# Motor-Driver.net
KiCad netlist of a schematic drawn in EAGLE
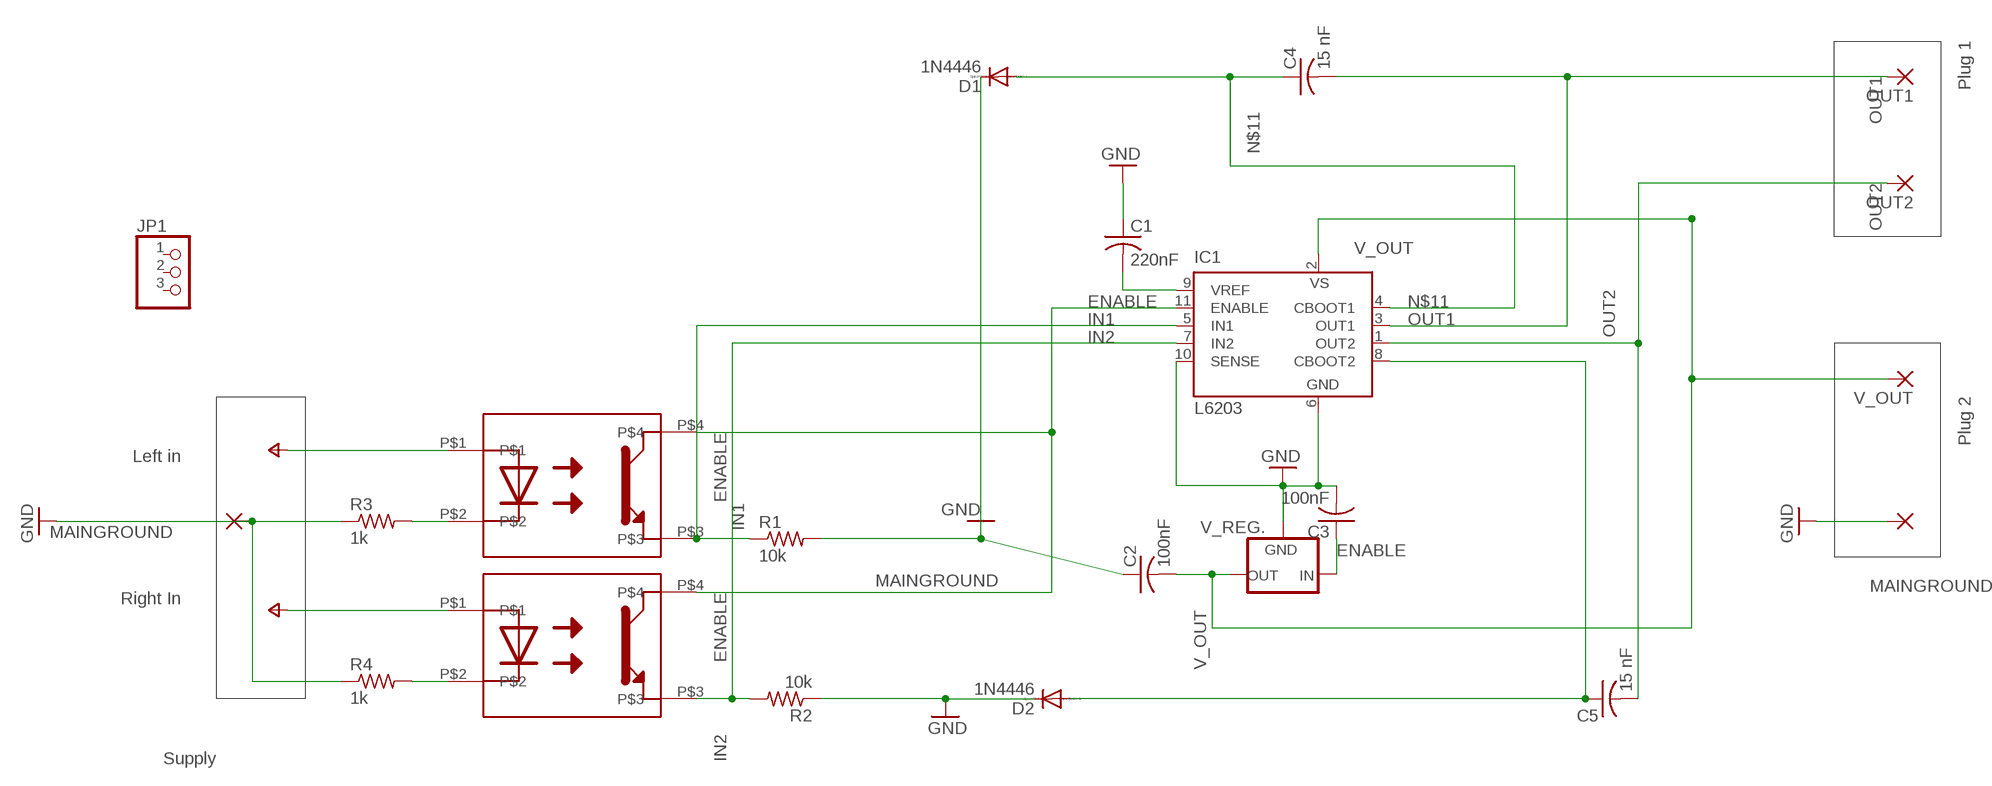
[diagram p0: schematic, sheet 1]

(export (version "E")
  (design (tool "Eeschema 10.0.6"))
  (components
    (comp (ref "C1")
      (value "220nF")
      (footprint "eagle-import:C075-032X103")
      (libsource (lib "eagle-import") (part "C-US075-032X103"))
    )
    (comp (ref "C2")
      (value "100nF")
      (footprint "eagle-import:C075-032X103")
      (libsource (lib "eagle-import") (part "C-US075-032X103"))
    )
    (comp (ref "C3")
      (value "100nF")
      (footprint "eagle-import:C075-032X103")
      (libsource (lib "eagle-import") (part "C-US075-032X103"))
    )
    (comp (ref "C4")
      (value "15 nF")
      (footprint "eagle-import:C075-032X103")
      (libsource (lib "eagle-import") (part "C-US075-032X103"))
    )
    (comp (ref "C5")
      (value "15 nF")
      (footprint "eagle-import:C075-032X103")
      (libsource (lib "eagle-import") (part "C-US075-032X103"))
    )
    (comp (ref "D1")
      (value "1N4446")
      (footprint "eagle-import:DO35-10")
      (libsource (lib "eagle-import") (part "1N4446"))
    )
    (comp (ref "D2")
      (value "1N4446")
      (footprint "eagle-import:DO35-10")
      (libsource (lib "eagle-import") (part "1N4446"))
    )
    (comp (ref "IC1")
      (value "L6203")
      (footprint "eagle-import:MULTIWATT-11")
      (libsource (lib "eagle-import") (part "L6203"))
    )
    (comp (ref "JP1")
      (value "PINHD-1X3")
      (footprint "eagle-import:1X03")
      (libsource (lib "eagle-import") (part "PINHD-1X3"))
    )
    (comp (ref "MAINGROUND")
      (value "PAD-TERMINAL")
      (footprint "eagle-import:2,54_1,1")
      (libsource (lib "eagle-import") (part "PAD-TERMINAL"))
    )
    (comp (ref "OUT1")
      (value "PAD-TERMINAL")
      (footprint "eagle-import:2,54_1,1")
      (libsource (lib "eagle-import") (part "PAD-TERMINAL"))
    )
    (comp (ref "OUT2")
      (value "PAD-TERMINAL")
      (footprint "eagle-import:2,54_1,1")
      (libsource (lib "eagle-import") (part "PAD-TERMINAL"))
    )
    (comp (ref "OUT_GND")
      (value "PAD-TERMINAL")
      (footprint "eagle-import:2,54_1,1")
      (libsource (lib "eagle-import") (part "PAD-TERMINAL"))
    )
    (comp (ref "R1")
      (value "10k")
      (footprint "eagle-import:0204_7")
      (libsource (lib "eagle-import") (part "R-US_0204/7"))
    )
    (comp (ref "R2")
      (value "10k")
      (footprint "eagle-import:0204_7")
      (libsource (lib "eagle-import") (part "R-US_0204/7"))
    )
    (comp (ref "R3")
      (value "1k")
      (footprint "eagle-import:0204_7")
      (libsource (lib "eagle-import") (part "R-US_0204/7"))
    )
    (comp (ref "R4")
      (value "1k")
      (footprint "eagle-import:0204_7")
      (libsource (lib "eagle-import") (part "R-US_0204/7"))
    )
    (comp (ref "U$1")
      (value "TPL521")
      (footprint "eagle-import:TPL521")
      (libsource (lib "eagle-import") (part "TPL521"))
    )
    (comp (ref "U$2")
      (value "TPL521")
      (footprint "eagle-import:TPL521")
      (libsource (lib "eagle-import") (part "TPL521"))
    )
    (comp (ref "V_OUT")
      (value "PAD-TERMINAL")
      (footprint "eagle-import:2,54_1,1")
      (libsource (lib "eagle-import") (part "PAD-TERMINAL"))
    )
    (comp (ref "V_REG.")
      (value "V_REG_78XXTO-92_UNTESTED")
      (footprint "eagle-import:TO-92")
      (libsource (lib "eagle-import") (part "V_REG_78XXTO-92_UNTESTED"))
    )
  )
  (nets
    (net (code "1") (name "/ENABLE") (class "Default")
      (node (ref "C3") (pin "1") (pinfunction "1_1") (pintype "passive"))
      (node (ref "IC1") (pin "11") (pinfunction "ENABLE_11") (pintype "input"))
      (node (ref "U$1") (pin "P$4") (pinfunction "P$4_P$4") (pintype "bidirectional"))
      (node (ref "U$2") (pin "P$4") (pinfunction "P$4_P$4") (pintype "bidirectional"))
      (node (ref "V_REG.") (pin "3") (pinfunction "IN_3") (pintype "input"))
    )
    (net (code "2") (name "/IN1") (class "Default")
      (node (ref "IC1") (pin "5") (pinfunction "IN1_5") (pintype "input"))
      (node (ref "R1") (pin "1") (pinfunction "1_1") (pintype "passive"))
      (node (ref "U$1") (pin "P$3") (pinfunction "P$3_P$3") (pintype "bidirectional"))
    )
    (net (code "3") (name "/IN2") (class "Default")
      (node (ref "IC1") (pin "7") (pinfunction "IN2_7") (pintype "input"))
      (node (ref "R2") (pin "2") (pinfunction "2_2") (pintype "passive"))
      (node (ref "U$2") (pin "P$3") (pinfunction "P$3_P$3") (pintype "bidirectional"))
    )
    (net (code "4") (name "/N$11") (class "Default")
      (node (ref "C4") (pin "1") (pinfunction "1_1") (pintype "passive"))
      (node (ref "D1") (pin "A") (pinfunction "A_A") (pintype "passive"))
      (node (ref "IC1") (pin "4") (pinfunction "CBOOT1_4") (pintype "input"))
    )
    (net (code "5") (name "/OUT1") (class "Default")
      (node (ref "C4") (pin "2") (pinfunction "2_2") (pintype "passive"))
      (node (ref "IC1") (pin "3") (pinfunction "OUT1_3") (pintype "output"))
      (node (ref "OUT1") (pin "1") (pinfunction "P_1") (pintype "passive"))
    )
    (net (code "6") (name "/OUT2") (class "Default")
      (node (ref "C5") (pin "2") (pinfunction "2_2") (pintype "passive"))
      (node (ref "IC1") (pin "1") (pinfunction "OUT2_1") (pintype "output"))
      (node (ref "OUT2") (pin "1") (pinfunction "P_1") (pintype "passive"))
    )
    (net (code "7") (name "/V_OUT") (class "Default")
      (node (ref "C2") (pin "2") (pinfunction "2_2") (pintype "passive"))
      (node (ref "IC1") (pin "2") (pinfunction "VS_2") (pintype "power_in"))
      (node (ref "V_OUT") (pin "1") (pinfunction "P_1") (pintype "passive"))
      (node (ref "V_REG.") (pin "1") (pinfunction "OUT_1") (pintype "passive"))
    )
    (net (code "8") (name "GND") (class "Default")
      (node (ref "C1") (pin "1") (pinfunction "1_1") (pintype "passive"))
      (node (ref "C2") (pin "1") (pinfunction "1_1") (pintype "passive"))
      (node (ref "C3") (pin "2") (pinfunction "2_2") (pintype "passive"))
      (node (ref "D1") (pin "C") (pinfunction "C_C") (pintype "passive"))
      (node (ref "D2") (pin "C") (pinfunction "C_C") (pintype "passive"))
      (node (ref "IC1") (pin "10") (pinfunction "SENSE_10") (pintype "input"))
      (node (ref "IC1") (pin "6") (pinfunction "GND_6") (pintype "power_in"))
      (node (ref "MAINGROUND") (pin "1") (pinfunction "P_1") (pintype "passive"))
      (node (ref "OUT_GND") (pin "1") (pinfunction "P_1") (pintype "passive"))
      (node (ref "R1") (pin "2") (pinfunction "2_2") (pintype "passive"))
      (node (ref "R2") (pin "1") (pinfunction "1_1") (pintype "passive"))
      (node (ref "R3") (pin "1") (pinfunction "1_1") (pintype "passive"))
      (node (ref "R4") (pin "1") (pinfunction "1_1") (pintype "passive"))
      (node (ref "V_REG.") (pin "2") (pinfunction "GND_2") (pintype "input"))
    )
    (net (code "9") (name "Left in") (class "Default")
      (node (ref "U$1") (pin "P$1") (pinfunction "P$1_P$1") (pintype "bidirectional"))
    )
    (net (code "10") (name "Net-(IC1-CBOOT2)") (class "Default")
      (node (ref "C5") (pin "1") (pinfunction "1_1") (pintype "passive"))
      (node (ref "D2") (pin "A") (pinfunction "A_A") (pintype "passive"))
      (node (ref "IC1") (pin "8") (pinfunction "CBOOT2_8") (pintype "input"))
    )
    (net (code "11") (name "Net-(IC1-VREF)") (class "Default")
      (node (ref "C1") (pin "2") (pinfunction "2_2") (pintype "passive"))
      (node (ref "IC1") (pin "9") (pinfunction "VREF_9") (pintype "input"))
    )
    (net (code "12") (name "Net-(R3-Pad2)") (class "Default")
      (node (ref "R3") (pin "2") (pinfunction "2_2") (pintype "passive"))
      (node (ref "U$1") (pin "P$2") (pinfunction "P$2_P$2") (pintype "bidirectional"))
    )
    (net (code "13") (name "Net-(R4-Pad2)") (class "Default")
      (node (ref "R4") (pin "2") (pinfunction "2_2") (pintype "passive"))
      (node (ref "U$2") (pin "P$2") (pinfunction "P$2_P$2") (pintype "bidirectional"))
    )
    (net (code "14") (name "Right In") (class "Default")
      (node (ref "U$2") (pin "P$1") (pinfunction "P$1_P$1") (pintype "bidirectional"))
    )
    (net (code "15") (name "unconnected-(JP1-Pad1)") (class "Default")
      (node (ref "JP1") (pin "1") (pinfunction "1_1") (pintype "passive"))
    )
    (net (code "16") (name "unconnected-(JP1-Pad2)") (class "Default")
      (node (ref "JP1") (pin "2") (pinfunction "2_2") (pintype "passive"))
    )
    (net (code "17") (name "unconnected-(JP1-Pad3)") (class "Default")
      (node (ref "JP1") (pin "3") (pinfunction "3_3") (pintype "passive"))
    )
  )
)
